# Powersupply.net
KiCad netlist of a schematic drawn in Altium Designer
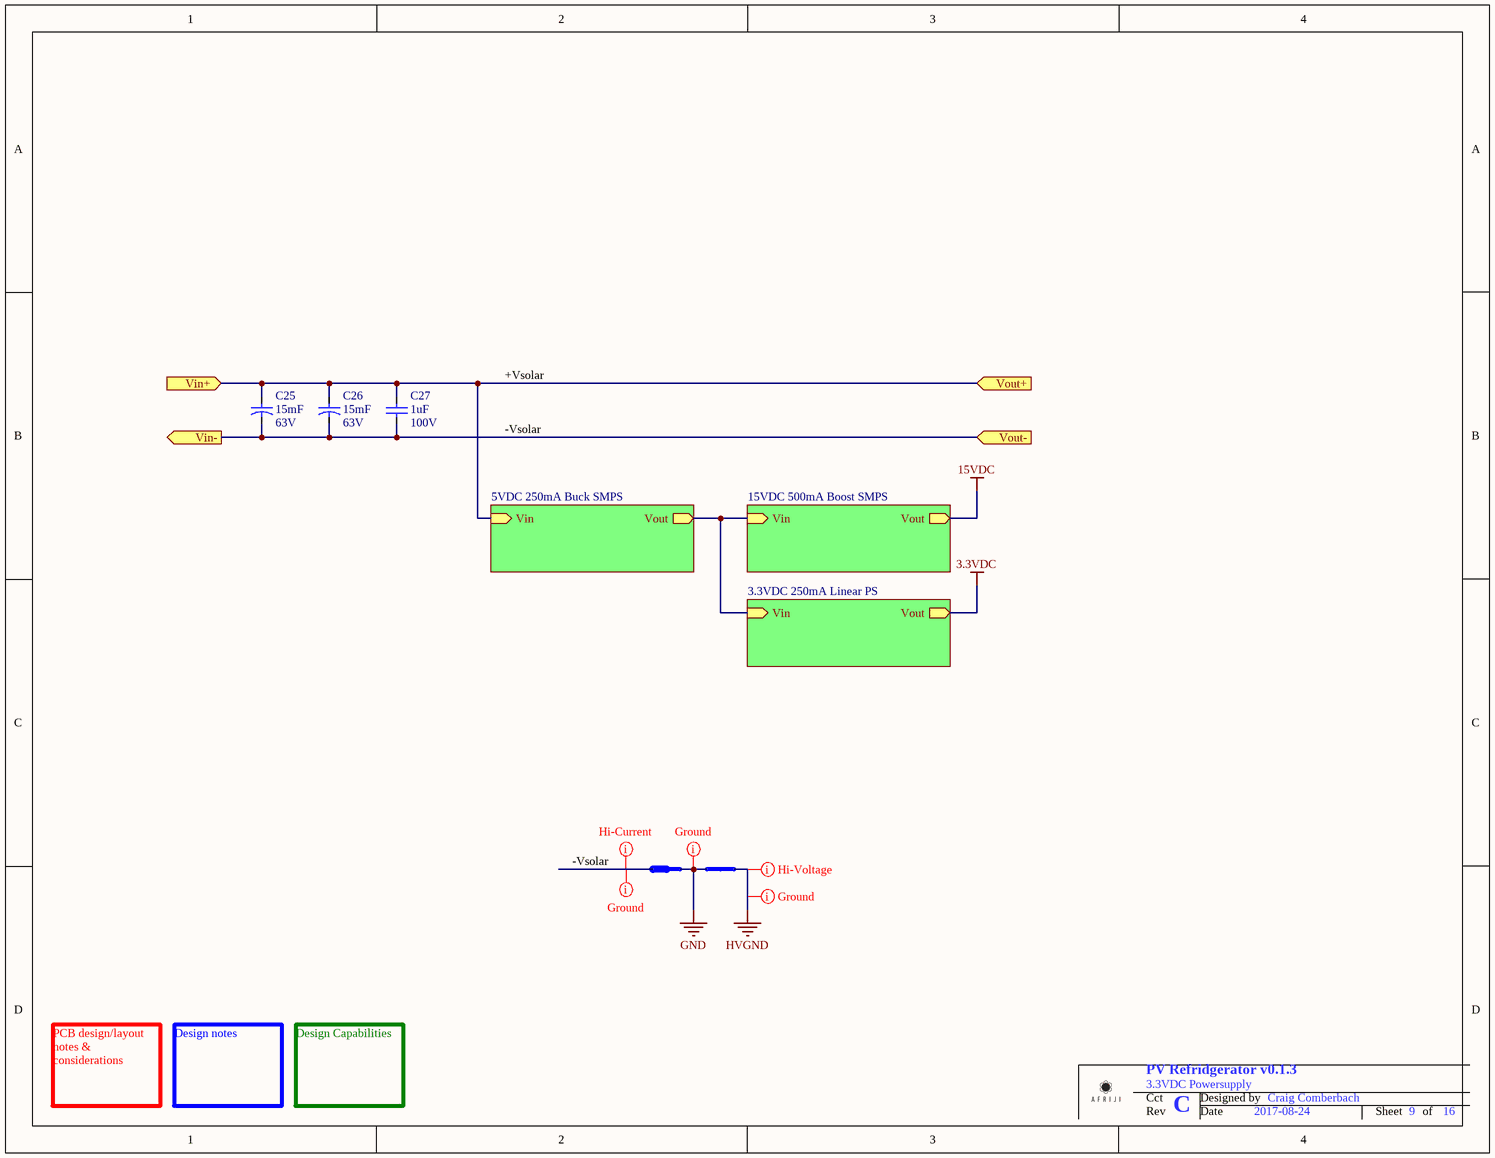
[diagram p0: Powersupply.SchDoc]

(export (version "E")
  (design (tool "Eeschema 10.0.6"))
  (components
    (comp (ref "C25")
      (value "15mF Radial 63V")
      (description "Polarized")
      (fields
        (field (name "MANUFACTURER") "United Chemi-Con")
        (field (name "MANUFACTURER PART NUMBER") "EKMH630VSN153MA63T")
        (field (name "CAPACITANCE") "15mF")
        (field (name "VOLTAGE") "63V")
      )
      (libsource (lib "Local Library") (part "15mF Radial 63V"))
    )
    (comp (ref "C26")
      (value "15mF Radial 63V")
      (description "Polarized")
      (fields
        (field (name "MANUFACTURER") "United Chemi-Con")
        (field (name "MANUFACTURER PART NUMBER") "EKMH630VSN153MA63T")
        (field (name "CAPACITANCE") "15mF")
        (field (name "VOLTAGE") "63V")
      )
      (libsource (lib "Local Library") (part "15mF Radial 63V"))
    )
    (comp (ref "C27")
      (value "1uF 1206 100V")
      (description "Non-polarized")
      (fields
        (field (name "MANUFACTURER") "Samsung Electro-Mechanics America, Inc.")
        (field (name "MANUFACTURER PART NUMBER") "CL31B105KCHNNNE")
        (field (name "VOLTAGE - RATED") "100V")
        (field (name "CAPACITIANCE") "1uF")
      )
      (libsource (lib "Local Library") (part "1uF 1206 100V"))
    )
    (comp (ref "NetTie2")
      (value "Net Tie - Same Size")
      (description "Ties two nets together")
      (libsource (lib "Local Library") (part "Net Tie - Same Size"))
    )
    (comp (ref "NetTie10")
      (value "Net Tie - Different Sizes")
      (description "Ties two nets together")
      (libsource (lib "Local Library") (part "Net Tie - Different Sizes"))
    )
  )
  (nets
    (net (code "1") (name "/+Vsolar") (class "Default")
      (node (ref "C25") (pin "1") (pinfunction "1_1") (pintype "passive"))
      (node (ref "C26") (pin "1") (pinfunction "1_1") (pintype "passive"))
      (node (ref "C27") (pin "1") (pinfunction "1_1") (pintype "passive"))
    )
    (net (code "2") (name "/-Vsolar") (class "Default")
      (node (ref "C25") (pin "2") (pinfunction "2_2") (pintype "passive"))
      (node (ref "C26") (pin "2") (pinfunction "2_2") (pintype "passive"))
      (node (ref "C27") (pin "2") (pinfunction "2_2") (pintype "passive"))
      (node (ref "NetTie10") (pin "2") (pinfunction "2_2") (pintype "passive"))
    )
    (net (code "6") (name "GND") (class "Default")
      (node (ref "NetTie10") (pin "1") (pinfunction "1_1") (pintype "passive"))
      (node (ref "NetTie2") (pin "2") (pinfunction "2_2") (pintype "passive"))
    )
    (net (code "7") (name "HVGND") (class "Default")
      (node (ref "NetTie2") (pin "1") (pinfunction "1_1") (pintype "passive"))
    )
  )
)
